# 04-MCU.net
KiCad netlist of a schematic drawn in Altium Designer
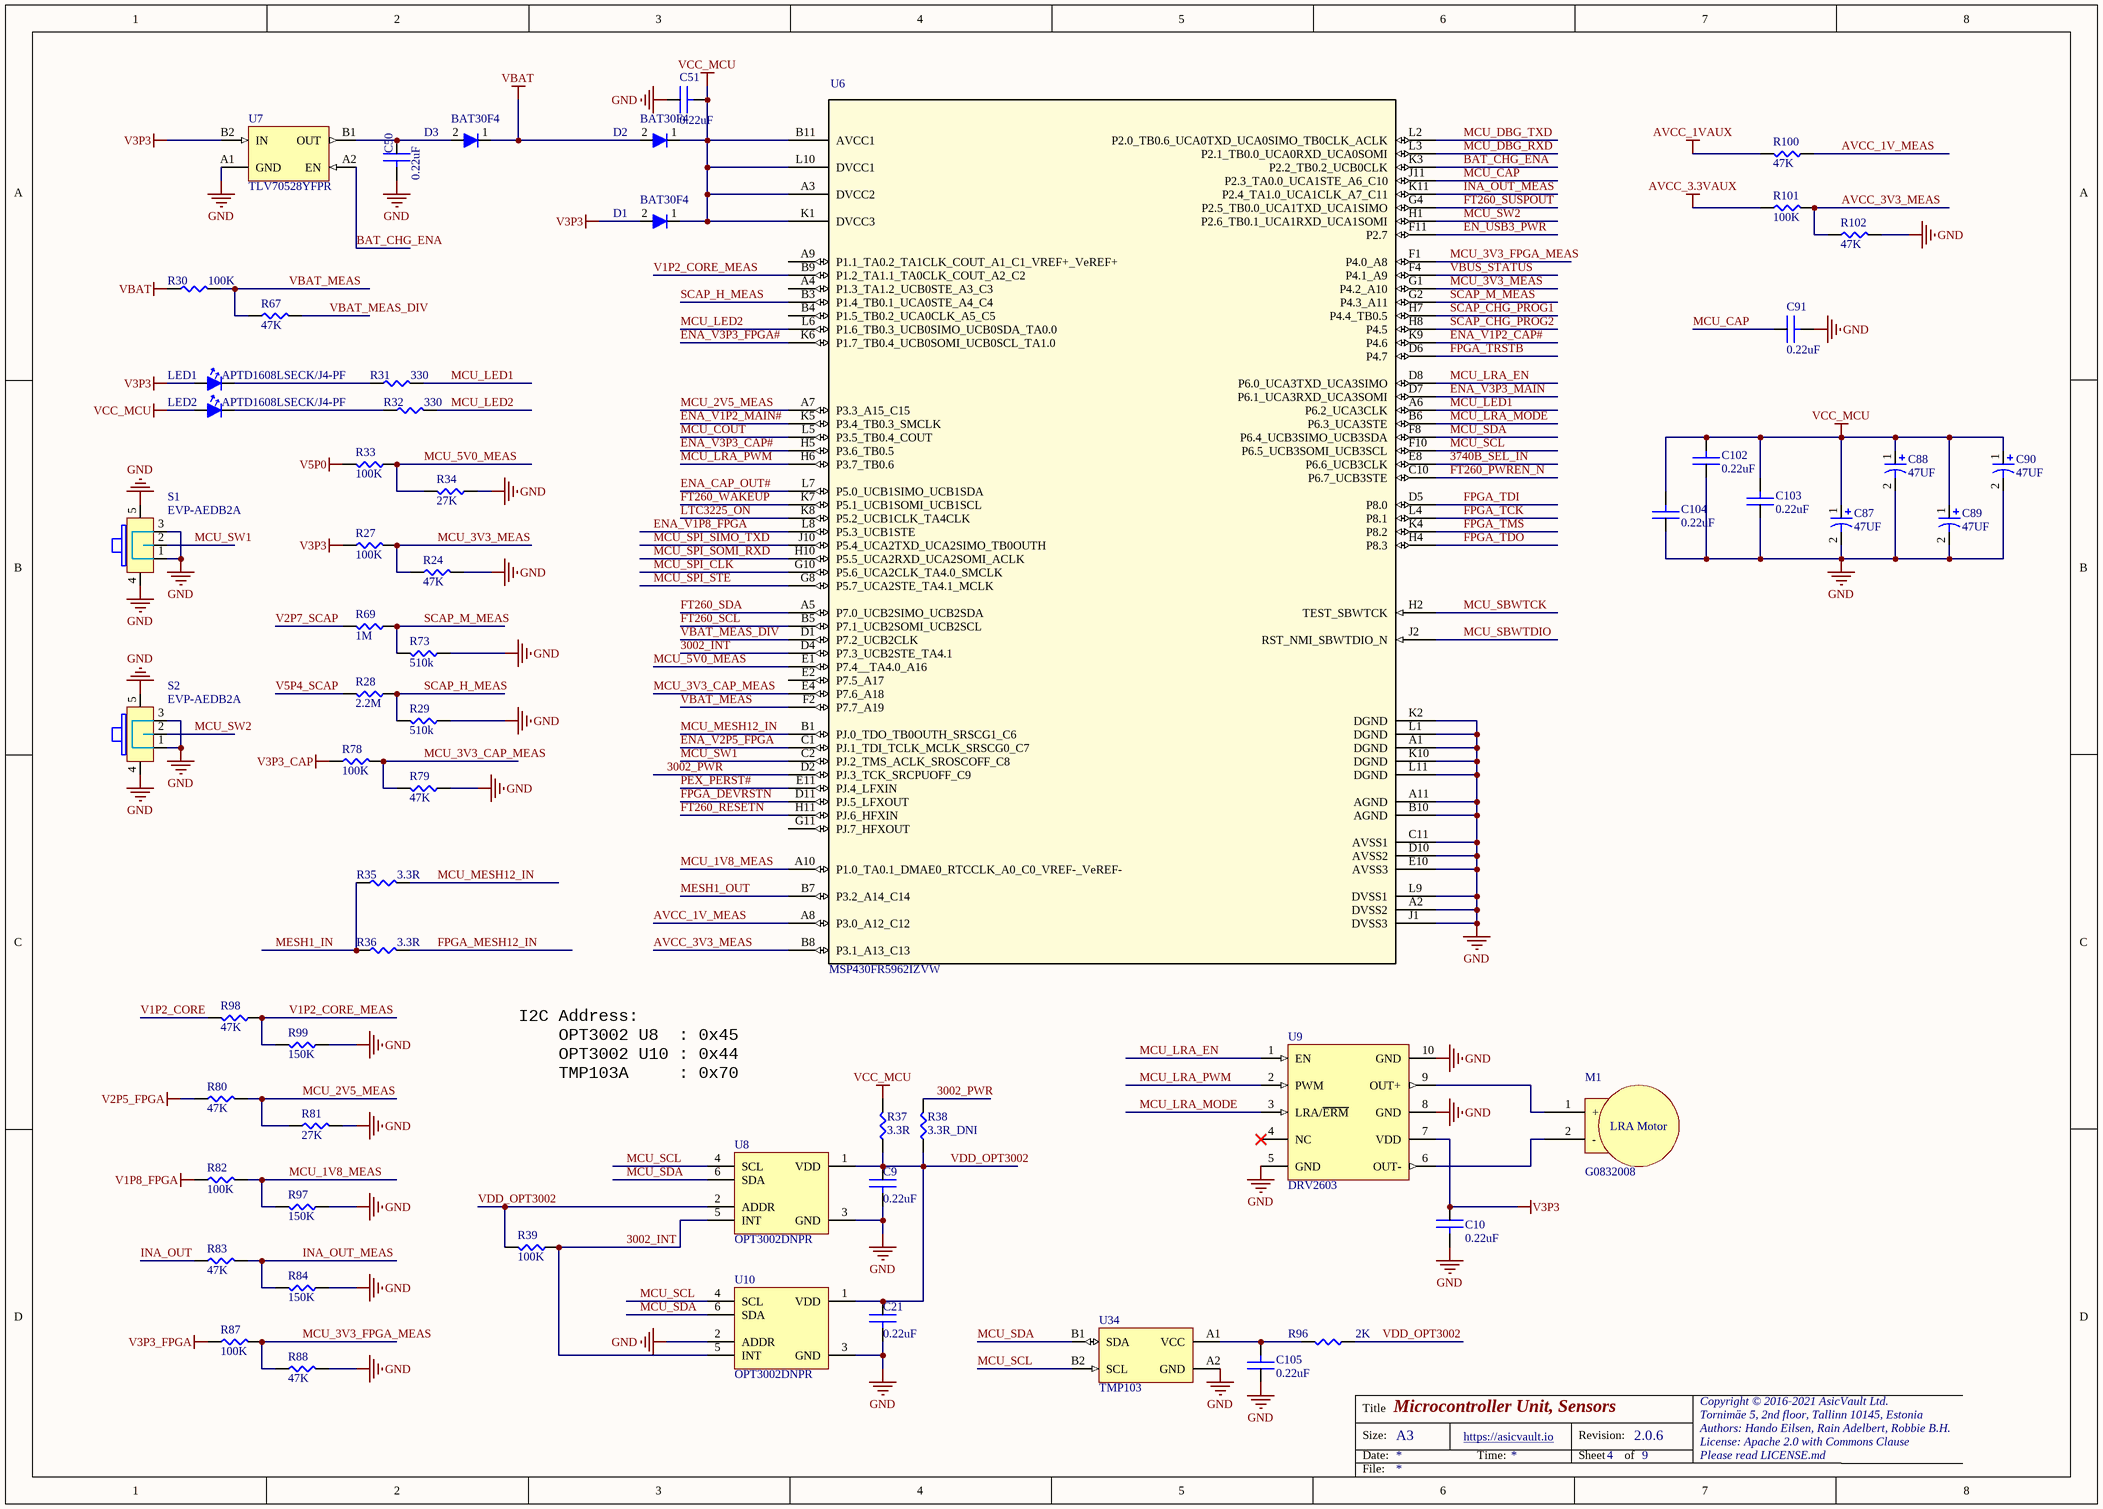
[diagram p0: 04-MCU.SchDoc]

(export (version "E")
  (design (tool "Eeschema 10.0.6"))
  (components
    (comp (ref "C9") (value "0.22uF") (footprint "C0201") (libsource (lib "AMOLED") (part "0.22uF/0201")))
    (comp (ref "C10") (value "0.22uF") (footprint "C0201") (libsource (lib "AMOLED") (part "0.22uF/0201")))
    (comp (ref "C21") (value "0.22uF") (footprint "C0201") (libsource (lib "AMOLED") (part "0.22uF/0201")))
    (comp (ref "C50") (value "0.22uF") (footprint "C0201") (libsource (lib "AMOLED") (part "0.22uF/0201")))
    (comp (ref "C51") (value "0.22uF") (footprint "C0201") (libsource (lib "AMOLED") (part "0.22uF/0201")))
    (comp (ref "C87") (value "47UF") (footprint "M0603C") (libsource (lib "AMOLED") (part "47UF/4V")))
    (comp (ref "C88") (value "47UF") (footprint "M0603C") (libsource (lib "AMOLED") (part "47UF/4V")))
    (comp (ref "C89") (value "47UF") (footprint "M0603C") (libsource (lib "AMOLED") (part "47UF/4V")))
    (comp (ref "C90") (value "47UF") (footprint "M0603C") (libsource (lib "AMOLED") (part "47UF/4V")))
    (comp (ref "C91") (value "0.22uF") (footprint "C0201") (libsource (lib "AMOLED") (part "0.22uF/0201")))
    (comp (ref "C102") (value "0.22uF") (footprint "C0201") (libsource (lib "AMOLED") (part "0.22uF/0201")))
    (comp (ref "C103") (value "0.22uF") (footprint "C0201") (libsource (lib "AMOLED") (part "0.22uF/0201")))
    (comp (ref "C104") (value "0.22uF") (footprint "C0201") (libsource (lib "AMOLED") (part "0.22uF/0201")))
    (comp (ref "C105") (value "0.22uF") (footprint "C0201") (libsource (lib "AMOLED") (part "0.22uF/0201")))
    (comp (ref "D1") (value "BAT30F4") (footprint "D0201") (libsource (lib "Control_Board") (part "BAT30F4")))
    (comp (ref "D2") (value "BAT30F4") (footprint "D0201") (libsource (lib "Control_Board") (part "BAT30F4")))
    (comp (ref "D3") (value "BAT30F4") (footprint "D0201") (libsource (lib "Control_Board") (part "BAT30F4")))
    (comp (ref "LED1")
      (value "APTD1608LSECK/J4-PF")
      (footprint "LED0603")
      (libsource (lib "Control_Board") (part "LED_ORGN_0603_KB"))
    )
    (comp (ref "LED2")
      (value "APTD1608LSECK/J4-PF")
      (footprint "LED0603")
      (libsource (lib "Control_Board") (part "LED_ORGN_0603_KB"))
    )
    (comp (ref "M1")
      (value "G0832008")
      (footprint "G0832008")
      (description "AC Motor Vibration, LRA 1.8VAC")
      (libsource (lib "PSD_V2_Schlib") (part "G0832008"))
    )
    (comp (ref "R24")
      (value "47K")
      (footprint "R0201")
      (libsource (lib "Control_Board") (part "47K/1%/0201"))
    )
    (comp (ref "R27")
      (value "100K")
      (footprint "R0201")
      (libsource (lib "Control_Board") (part "100K/1%/0201"))
    )
    (comp (ref "R28") (value "2.2M") (footprint "R0201") (libsource (lib "Board3") (part "2M2/1%/0201")))
    (comp (ref "R29") (value "510k") (footprint "R0201") (libsource (lib "Board3") (part "510K/1%/0201")))
    (comp (ref "R30")
      (value "100K")
      (footprint "R0201")
      (libsource (lib "Control_Board") (part "100K/1%/0201"))
    )
    (comp (ref "R31")
      (value "330")
      (footprint "R0201")
      (libsource (lib "Control_Board") (part "330/1%/0201"))
    )
    (comp (ref "R32")
      (value "330")
      (footprint "R0201")
      (libsource (lib "Control_Board") (part "330/1%/0201"))
    )
    (comp (ref "R33")
      (value "100K")
      (footprint "R0201")
      (libsource (lib "Control_Board") (part "100K/1%/0201"))
    )
    (comp (ref "R34")
      (value "27K")
      (footprint "R0201")
      (libsource (lib "Control_Board") (part "27K/1%/0201"))
    )
    (comp (ref "R35")
      (value "3.3R")
      (footprint "R0201")
      (libsource (lib "Control_Board") (part "3.3R/1%/0201"))
    )
    (comp (ref "R36")
      (value "3.3R")
      (footprint "R0201")
      (libsource (lib "Control_Board") (part "3.3R/1%/0201"))
    )
    (comp (ref "R37")
      (value "3.3R")
      (footprint "R0201")
      (libsource (lib "Control_Board") (part "3.3R/1%/0201"))
    )
    (comp (ref "R38")
      (value "3.3R_DNI")
      (footprint "R0201")
      (libsource (lib "Control_Board") (part "3.3R/1%/0201"))
    )
    (comp (ref "R39")
      (value "100K")
      (footprint "R0201")
      (libsource (lib "Control_Board") (part "100K/1%/0201"))
    )
    (comp (ref "R67")
      (value "47K")
      (footprint "R0201")
      (libsource (lib "Control_Board") (part "47K/1%/0201"))
    )
    (comp (ref "R69") (value "1M") (footprint "R0201") (libsource (lib "Control_Board") (part "1M/1%/0201")))
    (comp (ref "R73") (value "510k") (footprint "R0201") (libsource (lib "Board3") (part "510K/1%/0201")))
    (comp (ref "R78")
      (value "100K")
      (footprint "R0201")
      (libsource (lib "Control_Board") (part "100K/1%/0201"))
    )
    (comp (ref "R79")
      (value "47K")
      (footprint "R0201")
      (libsource (lib "Control_Board") (part "47K/1%/0201"))
    )
    (comp (ref "R80")
      (value "47K")
      (footprint "R0201")
      (libsource (lib "Control_Board") (part "47K/1%/0201"))
    )
    (comp (ref "R81")
      (value "27K")
      (footprint "R0201")
      (libsource (lib "Control_Board") (part "27K/1%/0201"))
    )
    (comp (ref "R82")
      (value "100K")
      (footprint "R0201")
      (libsource (lib "Control_Board") (part "100K/1%/0201"))
    )
    (comp (ref "R83")
      (value "47K")
      (footprint "R0201")
      (libsource (lib "Control_Board") (part "47K/1%/0201"))
    )
    (comp (ref "R84")
      (value "150K")
      (footprint "R0201")
      (libsource (lib "Control_Board") (part "150K/1%/0201"))
    )
    (comp (ref "R87")
      (value "100K")
      (footprint "R0201")
      (libsource (lib "Control_Board") (part "100K/1%/0201"))
    )
    (comp (ref "R88")
      (value "47K")
      (footprint "R0201")
      (libsource (lib "Control_Board") (part "47K/1%/0201"))
    )
    (comp (ref "R96") (value "2K") (footprint "R0201") (libsource (lib "Control_Board") (part "2K/1%/0201")))
    (comp (ref "R97")
      (value "150K")
      (footprint "R0201")
      (libsource (lib "Control_Board") (part "150K/1%/0201"))
    )
    (comp (ref "R98")
      (value "47K")
      (footprint "R0201")
      (libsource (lib "Control_Board") (part "47K/1%/0201"))
    )
    (comp (ref "R99")
      (value "150K")
      (footprint "R0201")
      (libsource (lib "Control_Board") (part "150K/1%/0201"))
    )
    (comp (ref "R100")
      (value "47K")
      (footprint "R0201")
      (libsource (lib "Control_Board") (part "47K/1%/0201"))
    )
    (comp (ref "R101")
      (value "100K")
      (footprint "R0201")
      (libsource (lib "Control_Board") (part "100K/1%/0201"))
    )
    (comp (ref "R102")
      (value "47K")
      (footprint "R0201")
      (libsource (lib "Control_Board") (part "47K/1%/0201"))
    )
    (comp (ref "S1")
      (value "EVP-AEDB2A")
      (footprint "EVP-AEDB2A")
      (libsource (lib "AMOLED") (part "EVP-AEDB2A"))
    )
    (comp (ref "S2")
      (value "EVP-AEDB2A")
      (footprint "EVP-AEDB2A")
      (libsource (lib "AMOLED") (part "EVP-AEDB2A"))
    )
    (comp (ref "U6")
      (value "MSP430FR5962IZVW")
      (footprint "ZVW0087A")
      (libsource (lib "Board3") (part "MSP430FR5962IZVW"))
    )
    (comp (ref "U7")
      (value "TLV70528YFPR")
      (footprint "DSBGA4")
      (description "200mA LDO, DSBGA")
      (libsource (lib "PSD_V2_Schlib") (part "TLV70528YFPR"))
    )
    (comp (ref "U8")
      (value "OPT3002DNPR")
      (footprint "USON6")
      (libsource (lib "AMOLED") (part "OPT3002DNPR"))
    )
    (comp (ref "U9")
      (value "DRV2603")
      (footprint "PWQFN-N10")
      (description "Haptic Drive for ERM and LRA")
      (libsource (lib "PSD_V2_Schlib") (part "DRV2603"))
    )
    (comp (ref "U10")
      (value "OPT3002DNPR")
      (footprint "USON6")
      (libsource (lib "AMOLED") (part "OPT3002DNPR"))
    )
    (comp (ref "U34")
      (value "TMP103")
      (footprint "DSBGA4")
      (description "SMBus Digital Temperature Sensor")
      (libsource (lib "PSD_V2_Schlib") (part "TMP103AYFFR"))
    )
  )
  (nets
    (net (code "1") (name "/3002_INT") (class "Default")
      (node (ref "R39") (pin "1") (pinfunction "1_1") (pintype "passive"))
      (node (ref "U10") (pin "5") (pinfunction "INT_5") (pintype "passive"))
      (node (ref "U6") (pin "D4") (pinfunction "P7.3_UCB2STE_TA4.1_D4") (pintype "bidirectional"))
      (node (ref "U8") (pin "5") (pinfunction "INT_5") (pintype "passive"))
    )
    (net (code "2") (name "/3002_PWR") (class "Default")
      (node (ref "R38") (pin "2") (pinfunction "2_2") (pintype "passive"))
      (node (ref "U6") (pin "D2") (pinfunction "PJ.3_TCK_SRCPUOFF_C9_D2") (pintype "bidirectional"))
    )
    (net (code "3") (name "/3740B_SEL_IN") (class "Default")
      (node (ref "U6") (pin "E8") (pinfunction "P6.6_UCB3CLK_E8") (pintype "bidirectional"))
    )
    (net (code "4") (name "/AVCC_1V_MEAS") (class "Default")
      (node (ref "R100") (pin "1") (pinfunction "1_1") (pintype "passive"))
      (node (ref "U6") (pin "A8") (pinfunction "P3.0_A12_C12_A8") (pintype "bidirectional"))
    )
    (net (code "5") (name "/AVCC_3V3_MEAS") (class "Default")
      (node (ref "R101") (pin "2") (pinfunction "2_2") (pintype "passive"))
      (node (ref "R102") (pin "1") (pinfunction "1_1") (pintype "passive"))
      (node (ref "U6") (pin "B8") (pinfunction "P3.1_A13_C13_B8") (pintype "bidirectional"))
    )
    (net (code "6") (name "/BAT_CHG_ENA") (class "Default")
      (node (ref "U6") (pin "K3") (pinfunction "P2.2_TB0.2_UCB0CLK_K3") (pintype "bidirectional"))
      (node (ref "U7") (pin "A2") (pinfunction "EN_A2") (pintype "input"))
    )
    (net (code "7") (name "/ENA_CAP_OUT#") (class "Default")
      (node (ref "U6") (pin "L7") (pinfunction "P5.0_UCB1SIMO_UCB1SDA_L7") (pintype "bidirectional"))
    )
    (net (code "8") (name "/ENA_V1P2_CAP#") (class "Default")
      (node (ref "U6") (pin "K9") (pinfunction "P4.6_K9") (pintype "bidirectional"))
    )
    (net (code "9") (name "/ENA_V1P2_MAIN#") (class "Default")
      (node (ref "U6") (pin "K5") (pinfunction "P3.4_TB0.3_SMCLK_K5") (pintype "bidirectional"))
    )
    (net (code "10") (name "/ENA_V1P8_FPGA") (class "Default")
      (node (ref "U6") (pin "L8") (pinfunction "P5.3_UCB1STE_L8") (pintype "bidirectional"))
    )
    (net (code "11") (name "/ENA_V2P5_FPGA") (class "Default")
      (node (ref "U6") (pin "C1") (pinfunction "PJ.1_TDI_TCLK_MCLK_SRSCG0_C7_C1") (pintype "bidirectional"))
    )
    (net (code "12") (name "/ENA_V3P3_CAP#") (class "Default")
      (node (ref "U6") (pin "H5") (pinfunction "P3.6_TB0.5_H5") (pintype "bidirectional"))
    )
    (net (code "13") (name "/ENA_V3P3_FPGA#") (class "Default")
      (node (ref "U6") (pin "K6") (pinfunction "P1.7_TB0.4_UCB0SOMI_UCB0SCL_TA1.0_K6") (pintype "bidirectional"))
    )
    (net (code "14") (name "/ENA_V3P3_MAIN") (class "Default")
      (node (ref "U6") (pin "D7") (pinfunction "P6.1_UCA3RXD_UCA3SOMI_D7") (pintype "bidirectional"))
    )
    (net (code "15") (name "/EN_USB3_PWR") (class "Default")
      (node (ref "U6") (pin "F11") (pinfunction "P2.7_F11") (pintype "bidirectional"))
    )
    (net (code "16") (name "/FPGA_DEVRSTN") (class "Default")
      (node (ref "U6") (pin "D11") (pinfunction "PJ.5_LFXOUT_D11") (pintype "bidirectional"))
    )
    (net (code "17") (name "/FPGA_MESH12_IN") (class "Default")
      (node (ref "R36") (pin "2") (pinfunction "2_2") (pintype "passive"))
    )
    (net (code "18") (name "/FPGA_TCK") (class "Default")
      (node (ref "U6") (pin "L4") (pinfunction "P8.1_L4") (pintype "bidirectional"))
    )
    (net (code "19") (name "/FPGA_TDI") (class "Default")
      (node (ref "U6") (pin "D5") (pinfunction "P8.0_D5") (pintype "bidirectional"))
    )
    (net (code "20") (name "/FPGA_TDO") (class "Default")
      (node (ref "U6") (pin "H4") (pinfunction "P8.3_H4") (pintype "bidirectional"))
    )
    (net (code "21") (name "/FPGA_TMS") (class "Default")
      (node (ref "U6") (pin "K4") (pinfunction "P8.2_K4") (pintype "bidirectional"))
    )
    (net (code "22") (name "/FPGA_TRSTB") (class "Default")
      (node (ref "U6") (pin "D6") (pinfunction "P4.7_D6") (pintype "bidirectional"))
    )
    (net (code "23") (name "/FT260_PWREN_N") (class "Default")
      (node (ref "U6") (pin "C10") (pinfunction "P6.7_UCB3STE_C10") (pintype "bidirectional"))
    )
    (net (code "24") (name "/FT260_RESETN") (class "Default")
      (node (ref "U6") (pin "H11") (pinfunction "PJ.6_HFXIN_H11") (pintype "bidirectional"))
    )
    (net (code "25") (name "/FT260_SCL") (class "Default")
      (node (ref "U6") (pin "B5") (pinfunction "P7.1_UCB2SOMI_UCB2SCL_B5") (pintype "bidirectional"))
    )
    (net (code "26") (name "/FT260_SDA") (class "Default")
      (node (ref "U6") (pin "A5") (pinfunction "P7.0_UCB2SIMO_UCB2SDA_A5") (pintype "bidirectional"))
    )
    (net (code "27") (name "/FT260_SUSPOUT") (class "Default")
      (node (ref "U6") (pin "G4") (pinfunction "P2.5_TB0.0_UCA1TXD_UCA1SIMO_G4") (pintype "bidirectional"))
    )
    (net (code "28") (name "/FT260_WAKEUP") (class "Default")
      (node (ref "U6") (pin "K7") (pinfunction "P5.1_UCB1SOMI_UCB1SCL_K7") (pintype "bidirectional"))
    )
    (net (code "29") (name "/INA_OUT") (class "Default")
      (node (ref "R83") (pin "1") (pinfunction "1_1") (pintype "passive"))
    )
    (net (code "30") (name "/INA_OUT_MEAS") (class "Default")
      (node (ref "R83") (pin "2") (pinfunction "2_2") (pintype "passive"))
      (node (ref "R84") (pin "2") (pinfunction "2_2") (pintype "passive"))
      (node (ref "U6") (pin "K11") (pinfunction "P2.4_TA1.0_UCA1CLK_A7_C11_K11") (pintype "bidirectional"))
    )
    (net (code "31") (name "/LTC3225_ON") (class "Default")
      (node (ref "U6") (pin "K8") (pinfunction "P5.2_UCB1CLK_TA4CLK_K8") (pintype "bidirectional"))
    )
    (net (code "32") (name "/MCU_1V8_MEAS") (class "Default")
      (node (ref "R82") (pin "2") (pinfunction "2_2") (pintype "passive"))
      (node (ref "R97") (pin "2") (pinfunction "2_2") (pintype "passive"))
      (node (ref "U6") (pin "A10") (pinfunction "P1.0_TA0.1_DMAE0_RTCCLK_A0_C0_VREF-_VeREF-_A10") (pintype "bidirectional"))
    )
    (net (code "33") (name "/MCU_2V5_MEAS") (class "Default")
      (node (ref "R80") (pin "2") (pinfunction "2_2") (pintype "passive"))
      (node (ref "R81") (pin "1") (pinfunction "1_1") (pintype "passive"))
      (node (ref "U6") (pin "A7") (pinfunction "P3.3_A15_C15_A7") (pintype "bidirectional"))
    )
    (net (code "34") (name "/MCU_3V3_CAP_MEAS") (class "Default")
      (node (ref "R78") (pin "2") (pinfunction "2_2") (pintype "passive"))
      (node (ref "R79") (pin "2") (pinfunction "2_2") (pintype "passive"))
      (node (ref "U6") (pin "E4") (pinfunction "P7.6_A18_E4") (pintype "bidirectional"))
    )
    (net (code "35") (name "/MCU_3V3_FPGA_MEAS") (class "Default")
      (node (ref "R87") (pin "2") (pinfunction "2_2") (pintype "passive"))
      (node (ref "R88") (pin "1") (pinfunction "1_1") (pintype "passive"))
      (node (ref "U6") (pin "F1") (pinfunction "P4.0_A8_F1") (pintype "bidirectional"))
    )
    (net (code "36") (name "/MCU_3V3_MEAS") (class "Default")
      (node (ref "R24") (pin "1") (pinfunction "1_1") (pintype "passive"))
      (node (ref "R27") (pin "2") (pinfunction "2_2") (pintype "passive"))
      (node (ref "U6") (pin "G1") (pinfunction "P4.2_A10_G1") (pintype "bidirectional"))
    )
    (net (code "37") (name "/MCU_5V0_MEAS") (class "Default")
      (node (ref "R33") (pin "1") (pinfunction "1_1") (pintype "passive"))
      (node (ref "R34") (pin "2") (pinfunction "2_2") (pintype "passive"))
      (node (ref "U6") (pin "E1") (pinfunction "P7.4__TA4.0_A16_E1") (pintype "bidirectional"))
    )
    (net (code "38") (name "/MCU_CAP") (class "Default")
      (node (ref "C91") (pin "1") (pinfunction "1_1") (pintype "passive"))
      (node (ref "U6") (pin "J11") (pinfunction "P2.3_TA0.0_UCA1STE_A6_C10_J11") (pintype "bidirectional"))
    )
    (net (code "39") (name "/MCU_COUT") (class "Default")
      (node (ref "U6") (pin "L5") (pinfunction "P3.5_TB0.4_COUT_L5") (pintype "bidirectional"))
    )
    (net (code "40") (name "/MCU_DBG_RXD") (class "Default")
      (node (ref "U6") (pin "L3") (pinfunction "P2.1_TB0.0_UCA0RXD_UCA0SOMI_L3") (pintype "bidirectional"))
    )
    (net (code "41") (name "/MCU_DBG_TXD") (class "Default")
      (node (ref "U6") (pin "L2") (pinfunction "P2.0_TB0.6_UCA0TXD_UCA0SIMO_TB0CLK_ACLK_L2") (pintype "bidirectional"))
    )
    (net (code "42") (name "/MCU_LED1") (class "Default")
      (node (ref "R31") (pin "2") (pinfunction "2_2") (pintype "passive"))
      (node (ref "U6") (pin "A6") (pinfunction "P6.2_UCA3CLK_A6") (pintype "bidirectional"))
    )
    (net (code "43") (name "/MCU_LED2") (class "Default")
      (node (ref "R32") (pin "2") (pinfunction "2_2") (pintype "passive"))
      (node (ref "U6") (pin "L6") (pinfunction "P1.6_TB0.3_UCB0SIMO_UCB0SDA_TA0.0_L6") (pintype "bidirectional"))
    )
    (net (code "44") (name "/MCU_LRA_EN") (class "Default")
      (node (ref "U6") (pin "D8") (pinfunction "P6.0_UCA3TXD_UCA3SIMO_D8") (pintype "bidirectional"))
      (node (ref "U9") (pin "1") (pinfunction "EN_1") (pintype "input"))
    )
    (net (code "45") (name "/MCU_LRA_MODE") (class "Default")
      (node (ref "U6") (pin "B6") (pinfunction "P6.3_UCA3STE_B6") (pintype "bidirectional"))
      (node (ref "U9") (pin "3") (pinfunction "LRA/~{ERM}_3") (pintype "input"))
    )
    (net (code "46") (name "/MCU_LRA_PWM") (class "Default")
      (node (ref "U6") (pin "H6") (pinfunction "P3.7_TB0.6_H6") (pintype "bidirectional"))
      (node (ref "U9") (pin "2") (pinfunction "PWM_2") (pintype "input"))
    )
    (net (code "47") (name "/MCU_MESH12_IN") (class "Default")
      (node (ref "R35") (pin "2") (pinfunction "2_2") (pintype "passive"))
      (node (ref "U6") (pin "B1") (pinfunction "PJ.0_TDO_TB0OUTH_SRSCG1_C6_B1") (pintype "bidirectional"))
    )
    (net (code "48") (name "/MCU_SBWTCK") (class "Default")
      (node (ref "U6") (pin "H2") (pinfunction "TEST_SBWTCK_H2") (pintype "input"))
    )
    (net (code "49") (name "/MCU_SBWTDIO") (class "Default")
      (node (ref "U6") (pin "J2") (pinfunction "RST_NMI_SBWTDIO_N_J2") (pintype "input"))
    )
    (net (code "50") (name "/MCU_SCL") (class "Default")
      (node (ref "U10") (pin "4") (pinfunction "SCL_4") (pintype "passive"))
      (node (ref "U34") (pin "B2") (pinfunction "SCL_B2") (pintype "input"))
      (node (ref "U6") (pin "F10") (pinfunction "P6.5_UCB3SOMI_UCB3SCL_F10") (pintype "bidirectional"))
      (node (ref "U8") (pin "4") (pinfunction "SCL_4") (pintype "passive"))
    )
    (net (code "51") (name "/MCU_SDA") (class "Default")
      (node (ref "U10") (pin "6") (pinfunction "SDA_6") (pintype "passive"))
      (node (ref "U34") (pin "B1") (pinfunction "SDA_B1") (pintype "bidirectional"))
      (node (ref "U6") (pin "F8") (pinfunction "P6.4_UCB3SIMO_UCB3SDA_F8") (pintype "bidirectional"))
      (node (ref "U8") (pin "6") (pinfunction "SDA_6") (pintype "passive"))
    )
    (net (code "52") (name "/MCU_SPI_CLK") (class "Default")
      (node (ref "U6") (pin "G10") (pinfunction "P5.6_UCA2CLK_TA4.0_SMCLK_G10") (pintype "bidirectional"))
    )
    (net (code "53") (name "/MCU_SPI_SIMO_TXD") (class "Default")
      (node (ref "U6") (pin "J10") (pinfunction "P5.4_UCA2TXD_UCA2SIMO_TB0OUTH_J10") (pintype "bidirectional"))
    )
    (net (code "54") (name "/MCU_SPI_SOMI_RXD") (class "Default")
      (node (ref "U6") (pin "H10") (pinfunction "P5.5_UCA2RXD_UCA2SOMI_ACLK_H10") (pintype "bidirectional"))
    )
    (net (code "55") (name "/MCU_SPI_STE") (class "Default")
      (node (ref "U6") (pin "G8") (pinfunction "P5.7_UCA2STE_TA4.1_MCLK_G8") (pintype "bidirectional"))
    )
    (net (code "56") (name "/MCU_SW1") (class "Default")
      (node (ref "S1") (pin "2") (pinfunction "A2_2") (pintype "passive"))
      (node (ref "U6") (pin "C2") (pinfunction "PJ.2_TMS_ACLK_SROSCOFF_C8_C2") (pintype "bidirectional"))
    )
    (net (code "57") (name "/MCU_SW2") (class "Default")
      (node (ref "S2") (pin "2") (pinfunction "A2_2") (pintype "passive"))
      (node (ref "U6") (pin "H1") (pinfunction "P2.6_TB0.1_UCA1RXD_UCA1SOMI_H1") (pintype "bidirectional"))
    )
    (net (code "58") (name "/MESH1_IN") (class "Default")
      (node (ref "R35") (pin "1") (pinfunction "1_1") (pintype "passive"))
      (node (ref "R36") (pin "1") (pinfunction "1_1") (pintype "passive"))
    )
    (net (code "59") (name "/MESH1_OUT") (class "Default")
      (node (ref "U6") (pin "B7") (pinfunction "P3.2_A14_C14_B7") (pintype "bidirectional"))
    )
    (net (code "60") (name "/PEX_PERST#") (class "Default")
      (node (ref "U6") (pin "E11") (pinfunction "PJ.4_LFXIN_E11") (pintype "bidirectional"))
    )
    (net (code "61") (name "/SCAP_CHG_PROG1") (class "Default")
      (node (ref "U6") (pin "H7") (pinfunction "P4.4_TB0.5_H7") (pintype "bidirectional"))
    )
    (net (code "62") (name "/SCAP_CHG_PROG2") (class "Default")
      (node (ref "U6") (pin "H8") (pinfunction "P4.5_H8") (pintype "bidirectional"))
    )
    (net (code "63") (name "/SCAP_H_MEAS") (class "Default")
      (node (ref "R28") (pin "1") (pinfunction "1_1") (pintype "passive"))
      (node (ref "R29") (pin "2") (pinfunction "2_2") (pintype "passive"))
      (node (ref "U6") (pin "B3") (pinfunction "P1.4_TB0.1_UCA0STE_A4_C4_B3") (pintype "bidirectional"))
    )
    (net (code "64") (name "/SCAP_M_MEAS") (class "Default")
      (node (ref "R69") (pin "1") (pinfunction "1_1") (pintype "passive"))
      (node (ref "R73") (pin "2") (pinfunction "2_2") (pintype "passive"))
      (node (ref "U6") (pin "G2") (pinfunction "P4.3_A11_G2") (pintype "bidirectional"))
    )
    (net (code "65") (name "/V1P2_CORE") (class "Default")
      (node (ref "R98") (pin "2") (pinfunction "2_2") (pintype "passive"))
    )
    (net (code "66") (name "/V1P2_CORE_MEAS") (class "Default")
      (node (ref "R98") (pin "1") (pinfunction "1_1") (pintype "passive"))
      (node (ref "R99") (pin "2") (pinfunction "2_2") (pintype "passive"))
      (node (ref "U6") (pin "B9") (pinfunction "P1.2_TA1.1_TA0CLK_COUT_A2_C2_B9") (pintype "bidirectional"))
    )
    (net (code "67") (name "/V2P7_SCAP") (class "Default")
      (node (ref "R69") (pin "2") (pinfunction "2_2") (pintype "passive"))
    )
    (net (code "68") (name "/V5P4_SCAP") (class "Default")
      (node (ref "R28") (pin "2") (pinfunction "2_2") (pintype "passive"))
    )
    (net (code "69") (name "/VBAT_MEAS") (class "Default")
      (node (ref "R30") (pin "2") (pinfunction "2_2") (pintype "passive"))
      (node (ref "R67") (pin "1") (pinfunction "1_1") (pintype "passive"))
      (node (ref "U6") (pin "F2") (pinfunction "P7.7_A19_F2") (pintype "bidirectional"))
    )
    (net (code "70") (name "/VBAT_MEAS_DIV") (class "Default")
      (node (ref "R67") (pin "2") (pinfunction "2_2") (pintype "passive"))
      (node (ref "U6") (pin "D1") (pinfunction "P7.2_UCB2CLK_D1") (pintype "bidirectional"))
    )
    (net (code "71") (name "/VBUS_STATUS") (class "Default")
      (node (ref "U6") (pin "F4") (pinfunction "P4.1_A9_F4") (pintype "bidirectional"))
    )
    (net (code "72") (name "/VDD_OPT3002") (class "Default")
      (node (ref "C21") (pin "1") (pinfunction "1_1") (pintype "passive"))
      (node (ref "C9") (pin "1") (pinfunction "1_1") (pintype "passive"))
      (node (ref "R37") (pin "1") (pinfunction "1_1") (pintype "passive"))
      (node (ref "R38") (pin "1") (pinfunction "1_1") (pintype "passive"))
      (node (ref "R39") (pin "2") (pinfunction "2_2") (pintype "passive"))
      (node (ref "R96") (pin "1") (pinfunction "1_1") (pintype "passive"))
      (node (ref "U10") (pin "1") (pinfunction "VDD_1") (pintype "passive"))
      (node (ref "U8") (pin "1") (pinfunction "VDD_1") (pintype "passive"))
      (node (ref "U8") (pin "2") (pinfunction "ADDR_2") (pintype "passive"))
    )
    (net (code "73") (name "AVCC_1VAUX") (class "Default")
      (node (ref "R100") (pin "2") (pinfunction "2_2") (pintype "passive"))
    )
    (net (code "74") (name "AVCC_3.3VAUX") (class "Default")
      (node (ref "R101") (pin "1") (pinfunction "1_1") (pintype "passive"))
    )
    (net (code "75") (name "GND") (class "Default")
      (node (ref "C10") (pin "2") (pinfunction "2_2") (pintype "passive"))
      (node (ref "C102") (pin "1") (pinfunction "1_1") (pintype "passive"))
      (node (ref "C103") (pin "1") (pinfunction "1_1") (pintype "passive"))
      (node (ref "C104") (pin "1") (pinfunction "1_1") (pintype "passive"))
      (node (ref "C105") (pin "1") (pinfunction "1_1") (pintype "passive"))
      (node (ref "C21") (pin "2") (pinfunction "2_2") (pintype "passive"))
      (node (ref "C50") (pin "2") (pinfunction "2_2") (pintype "passive"))
      (node (ref "C51") (pin "1") (pinfunction "1_1") (pintype "passive"))
      (node (ref "C87") (pin "2") (pinfunction "2_2") (pintype "passive"))
      (node (ref "C88") (pin "2") (pinfunction "2_2") (pintype "passive"))
      (node (ref "C89") (pin "2") (pinfunction "2_2") (pintype "passive"))
      (node (ref "C9") (pin "2") (pinfunction "2_2") (pintype "passive"))
      (node (ref "C90") (pin "2") (pinfunction "2_2") (pintype "passive"))
      (node (ref "C91") (pin "2") (pinfunction "2_2") (pintype "passive"))
      (node (ref "R102") (pin "2") (pinfunction "2_2") (pintype "passive"))
      (node (ref "R24") (pin "2") (pinfunction "2_2") (pintype "passive"))
      (node (ref "R29") (pin "1") (pinfunction "1_1") (pintype "passive"))
      (node (ref "R34") (pin "1") (pinfunction "1_1") (pintype "passive"))
      (node (ref "R73") (pin "1") (pinfunction "1_1") (pintype "passive"))
      (node (ref "R79") (pin "1") (pinfunction "1_1") (pintype "passive"))
      (node (ref "R81") (pin "2") (pinfunction "2_2") (pintype "passive"))
      (node (ref "R84") (pin "1") (pinfunction "1_1") (pintype "passive"))
      (node (ref "R88") (pin "2") (pinfunction "2_2") (pintype "passive"))
      (node (ref "R97") (pin "1") (pinfunction "1_1") (pintype "passive"))
      (node (ref "R99") (pin "1") (pinfunction "1_1") (pintype "passive"))
      (node (ref "S1") (pin "1") (pinfunction "A1_1") (pintype "passive"))
      (node (ref "S1") (pin "3") (pinfunction "B1_3") (pintype "passive"))
      (node (ref "S1") (pin "4") (pinfunction "B2_4") (pintype "passive"))
      (node (ref "S1") (pin "5") (pinfunction "B2_5") (pintype "passive"))
      (node (ref "S2") (pin "1") (pinfunction "A1_1") (pintype "passive"))
      (node (ref "S2") (pin "3") (pinfunction "B1_3") (pintype "passive"))
      (node (ref "S2") (pin "4") (pinfunction "B2_4") (pintype "passive"))
      (node (ref "S2") (pin "5") (pinfunction "B2_5") (pintype "passive"))
      (node (ref "U10") (pin "2") (pinfunction "ADDR_2") (pintype "passive"))
      (node (ref "U10") (pin "3") (pinfunction "GND_3") (pintype "passive"))
      (node (ref "U34") (pin "A2") (pinfunction "GND_A2") (pintype "power_in"))
      (node (ref "U6") (pin "A1") (pinfunction "DGND_A1") (pintype "power_in"))
      (node (ref "U6") (pin "A11") (pinfunction "AGND_A11") (pintype "power_in"))
      (node (ref "U6") (pin "A2") (pinfunction "DVSS2_A2") (pintype "power_in"))
      (node (ref "U6") (pin "B10") (pinfunction "AGND_B10") (pintype "power_in"))
      (node (ref "U6") (pin "C11") (pinfunction "AVSS1_C11") (pintype "power_in"))
      (node (ref "U6") (pin "D10") (pinfunction "AVSS2_D10") (pintype "power_in"))
      (node (ref "U6") (pin "E10") (pinfunction "AVSS3_E10") (pintype "power_in"))
      (node (ref "U6") (pin "J1") (pinfunction "DVSS3_J1") (pintype "power_in"))
      (node (ref "U6") (pin "K10") (pinfunction "DGND_K10") (pintype "power_in"))
      (node (ref "U6") (pin "K2") (pinfunction "DGND_K2") (pintype "power_in"))
      (node (ref "U6") (pin "L1") (pinfunction "DGND_L1") (pintype "power_in"))
      (node (ref "U6") (pin "L11") (pinfunction "DGND_L11") (pintype "power_in"))
      (node (ref "U6") (pin "L9") (pinfunction "DVSS1_L9") (pintype "power_in"))
      (node (ref "U7") (pin "A1") (pinfunction "GND_A1") (pintype "power_in"))
      (node (ref "U8") (pin "3") (pinfunction "GND_3") (pintype "passive"))
      (node (ref "U9") (pin "10") (pinfunction "GND_10") (pintype "power_in"))
      (node (ref "U9") (pin "5") (pinfunction "GND_5") (pintype "power_in"))
      (node (ref "U9") (pin "8") (pinfunction "GND_8") (pintype "power_in"))
    )
    (net (code "76") (name "Net-(D3-A)") (class "Default")
      (node (ref "C50") (pin "1") (pinfunction "1_1") (pintype "passive"))
      (node (ref "D3") (pin "2") (pinfunction "A_2") (pintype "passive"))
      (node (ref "U7") (pin "B1") (pinfunction "OUT_B1") (pintype "output"))
    )
    (net (code "77") (name "Net-(LED1-K)") (class "Default")
      (node (ref "LED1") (pin "1") (pinfunction "K_1") (pintype "passive"))
      (node (ref "R31") (pin "1") (pinfunction "1_1") (pintype "passive"))
    )
    (net (code "78") (name "Net-(LED2-K)") (class "Default")
      (node (ref "LED2") (pin "1") (pinfunction "K_1") (pintype "passive"))
      (node (ref "R32") (pin "1") (pinfunction "1_1") (pintype "passive"))
    )
    (net (code "79") (name "Net-(M1-+)") (class "Default")
      (node (ref "M1") (pin "1") (pinfunction "+_1") (pintype "passive"))
      (node (ref "U9") (pin "9") (pinfunction "OUT+_9") (pintype "output"))
    )
    (net (code "80") (name "Net-(M1--)") (class "Default")
      (node (ref "M1") (pin "2") (pinfunction "-_2") (pintype "passive"))
      (node (ref "U9") (pin "6") (pinfunction "OUT-_6") (pintype "output"))
    )
    (net (code "81") (name "Net-(U34-VCC)") (class "Default")
      (node (ref "C105") (pin "2") (pinfunction "2_2") (pintype "passive"))
      (node (ref "R96") (pin "2") (pinfunction "2_2") (pintype "passive"))
      (node (ref "U34") (pin "A1") (pinfunction "VCC_A1") (pintype "power_in"))
    )
    (net (code "82") (name "V1P8_FPGA") (class "Default")
      (node (ref "R82") (pin "1") (pinfunction "1_1") (pintype "passive"))
    )
    (net (code "83") (name "V2P5_FPGA") (class "Default")
      (node (ref "R80") (pin "1") (pinfunction "1_1") (pintype "passive"))
    )
    (net (code "84") (name "V3P3") (class "Default")
      (node (ref "C10") (pin "1") (pinfunction "1_1") (pintype "passive"))
      (node (ref "D1") (pin "2") (pinfunction "A_2") (pintype "passive"))
      (node (ref "LED1") (pin "2") (pinfunction "A_2") (pintype "passive"))
      (node (ref "R27") (pin "1") (pinfunction "1_1") (pintype "passive"))
      (node (ref "U7") (pin "B2") (pinfunction "IN_B2") (pintype "input"))
      (node (ref "U9") (pin "7") (pinfunction "VDD_7") (pintype "power_in"))
    )
    (net (code "85") (name "V3P3_CAP") (class "Default")
      (node (ref "R78") (pin "1") (pinfunction "1_1") (pintype "passive"))
    )
    (net (code "86") (name "V3P3_FPGA") (class "Default")
      (node (ref "R87") (pin "1") (pinfunction "1_1") (pintype "passive"))
    )
    (net (code "87") (name "V5P0") (class "Default")
      (node (ref "R33") (pin "2") (pinfunction "2_2") (pintype "passive"))
    )
    (net (code "88") (name "VBAT") (class "Default")
      (node (ref "D2") (pin "2") (pinfunction "A_2") (pintype "passive"))
      (node (ref "D3") (pin "1") (pinfunction "K_1") (pintype "passive"))
      (node (ref "R30") (pin "1") (pinfunction "1_1") (pintype "passive"))
    )
    (net (code "89") (name "VCC_MCU") (class "Default")
      (node (ref "C102") (pin "2") (pinfunction "2_2") (pintype "passive"))
      (node (ref "C103") (pin "2") (pinfunction "2_2") (pintype "passive"))
      (node (ref "C104") (pin "2") (pinfunction "2_2") (pintype "passive"))
      (node (ref "C51") (pin "2") (pinfunction "2_2") (pintype "passive"))
      (node (ref "C87") (pin "1") (pinfunction "1_1") (pintype "passive"))
      (node (ref "C88") (pin "1") (pinfunction "1_1") (pintype "passive"))
      (node (ref "C89") (pin "1") (pinfunction "1_1") (pintype "passive"))
      (node (ref "C90") (pin "1") (pinfunction "1_1") (pintype "passive"))
      (node (ref "D1") (pin "1") (pinfunction "K_1") (pintype "passive"))
      (node (ref "D2") (pin "1") (pinfunction "K_1") (pintype "passive"))
      (node (ref "LED2") (pin "2") (pinfunction "A_2") (pintype "passive"))
      (node (ref "R37") (pin "2") (pinfunction "2_2") (pintype "passive"))
      (node (ref "U6") (pin "A3") (pinfunction "DVCC2_A3") (pintype "power_in"))
      (node (ref "U6") (pin "B11") (pinfunction "AVCC1_B11") (pintype "power_in"))
      (node (ref "U6") (pin "K1") (pinfunction "DVCC3_K1") (pintype "power_in"))
      (node (ref "U6") (pin "L10") (pinfunction "DVCC1_L10") (pintype "power_in"))
    )
    (net (code "90") (name "unconnected-(U6-P1.1_TA0.2_TA1CLK_COUT_A1_C1_VREF+_VeREF+-PadA9)") (class "Default")
      (node (ref "U6") (pin "A9") (pinfunction "P1.1_TA0.2_TA1CLK_COUT_A1_C1_VREF+_VeREF+_A9") (pintype "bidirectional"))
    )
    (net (code "91") (name "unconnected-(U6-P1.3_TA1.2_UCB0STE_A3_C3-PadA4)") (class "Default")
      (node (ref "U6") (pin "A4") (pinfunction "P1.3_TA1.2_UCB0STE_A3_C3_A4") (pintype "bidirectional"))
    )
    (net (code "92") (name "unconnected-(U6-P1.5_TB0.2_UCA0CLK_A5_C5-PadB4)") (class "Default")
      (node (ref "U6") (pin "B4") (pinfunction "P1.5_TB0.2_UCA0CLK_A5_C5_B4") (pintype "bidirectional"))
    )
    (net (code "93") (name "unconnected-(U6-P7.5_A17-PadE2)") (class "Default")
      (node (ref "U6") (pin "E2") (pinfunction "P7.5_A17_E2") (pintype "bidirectional"))
    )
    (net (code "94") (name "unconnected-(U6-PJ.7_HFXOUT-PadG11)") (class "Default")
      (node (ref "U6") (pin "G11") (pinfunction "PJ.7_HFXOUT_G11") (pintype "bidirectional"))
    )
    (net (code "95") (name "unconnected-(U9-NC-Pad4)") (class "Default")
      (node (ref "U9") (pin "4") (pinfunction "NC_4") (pintype "passive+no_connect"))
    )
  )
)
